# BoardA-USB.net
KiCad netlist of a schematic drawn in Altium Designer
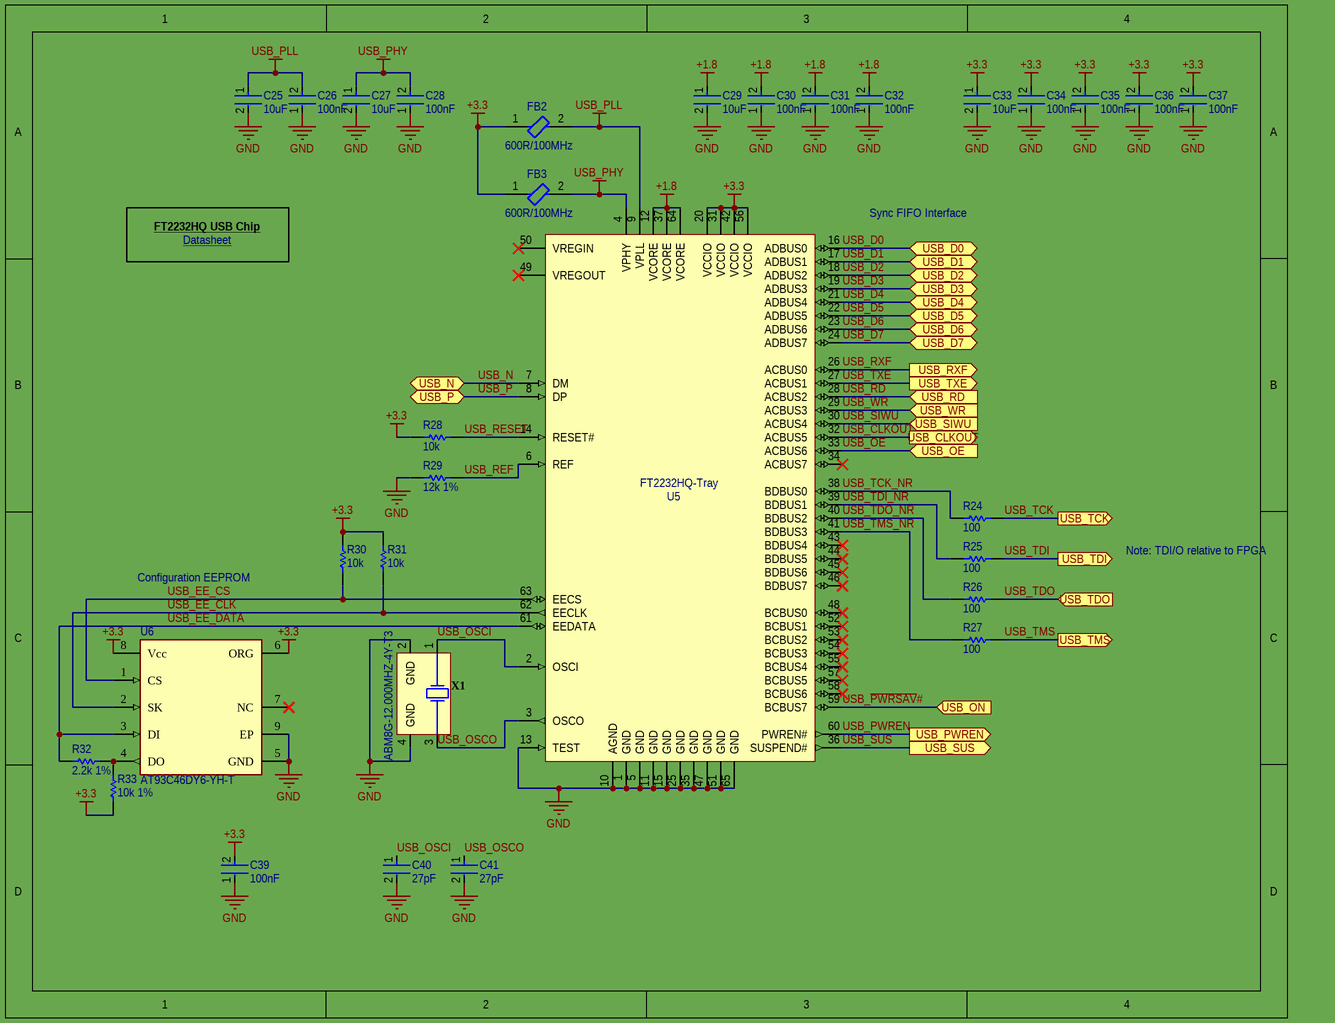
[diagram p0: BoardA-USB.SchDoc]

(export (version "E")
  (design (tool "Eeschema 10.0.6"))
  (components
    (comp (ref "C25")
      (value "10uF")
      (footprint "FP-CL05A106MP5NUNC-IPC_C")
      (description "CAP CER 10UF 10V X5R 0402")
      (fields
        (field (name "OCTOPART") "https://octopart.com/cl05a106mp5nunc-samsung-22457395")
        (field (name "TOLERANCE") "20%")
      )
      (libsource (lib "Altium Content Vault") (part "b4654b650e69147ec39a6b967a45e02"))
    )
    (comp (ref "C26")
      (value "100nF")
      (footprint "FP-GRM15-IPC_C")
      (description "CAP CER 0.1UF 16V X7R 0402")
      (fields (field (name "MANUFACTURER PART NUMBER") "GRM155R71C104KA88D") (field (name "TOLERANCE") "10%"))
      (libsource (lib "Altium Content Vault") (part "236180d848d6139a670b325ea6854c9"))
    )
    (comp (ref "C27")
      (value "10uF")
      (footprint "FP-CL05A106MP5NUNC-IPC_C")
      (description "CAP CER 10UF 10V X5R 0402")
      (fields
        (field (name "OCTOPART") "https://octopart.com/cl05a106mp5nunc-samsung-22457395")
        (field (name "TOLERANCE") "20%")
      )
      (libsource (lib "Altium Content Vault") (part "b4654b650e69147ec39a6b967a45e02"))
    )
    (comp (ref "C28")
      (value "100nF")
      (footprint "FP-GRM15-IPC_C")
      (description "CAP CER 0.1UF 16V X7R 0402")
      (fields (field (name "MANUFACTURER PART NUMBER") "GRM155R71C104KA88D") (field (name "TOLERANCE") "10%"))
      (libsource (lib "Altium Content Vault") (part "236180d848d6139a670b325ea6854c9"))
    )
    (comp (ref "C29")
      (value "10uF")
      (footprint "FP-CL05A106MP5NUNC-IPC_C")
      (description "CAP CER 10UF 10V X5R 0402")
      (fields
        (field (name "OCTOPART") "https://octopart.com/cl05a106mp5nunc-samsung-22457395")
        (field (name "TOLERANCE") "20%")
      )
      (libsource (lib "Altium Content Vault") (part "b4654b650e69147ec39a6b967a45e02"))
    )
    (comp (ref "C30")
      (value "100nF")
      (footprint "FP-GRM15-IPC_C")
      (description "CAP CER 0.1UF 16V X7R 0402")
      (fields (field (name "MANUFACTURER PART NUMBER") "GRM155R71C104KA88D") (field (name "TOLERANCE") "10%"))
      (libsource (lib "Altium Content Vault") (part "236180d848d6139a670b325ea6854c9"))
    )
    (comp (ref "C31")
      (value "100nF")
      (footprint "FP-GRM15-IPC_C")
      (description "CAP CER 0.1UF 16V X7R 0402")
      (fields (field (name "MANUFACTURER PART NUMBER") "GRM155R71C104KA88D") (field (name "TOLERANCE") "10%"))
      (libsource (lib "Altium Content Vault") (part "236180d848d6139a670b325ea6854c9"))
    )
    (comp (ref "C32")
      (value "100nF")
      (footprint "FP-GRM15-IPC_C")
      (description "CAP CER 0.1UF 16V X7R 0402")
      (fields (field (name "MANUFACTURER PART NUMBER") "GRM155R71C104KA88D") (field (name "TOLERANCE") "10%"))
      (libsource (lib "Altium Content Vault") (part "236180d848d6139a670b325ea6854c9"))
    )
    (comp (ref "C33")
      (value "10uF")
      (footprint "FP-CL05A106MP5NUNC-IPC_C")
      (description "CAP CER 10UF 10V X5R 0402")
      (fields
        (field (name "OCTOPART") "https://octopart.com/cl05a106mp5nunc-samsung-22457395")
        (field (name "TOLERANCE") "20%")
      )
      (libsource (lib "Altium Content Vault") (part "b4654b650e69147ec39a6b967a45e02"))
    )
    (comp (ref "C34")
      (value "100nF")
      (footprint "FP-GRM15-IPC_C")
      (description "CAP CER 0.1UF 16V X7R 0402")
      (fields (field (name "MANUFACTURER PART NUMBER") "GRM155R71C104KA88D") (field (name "TOLERANCE") "10%"))
      (libsource (lib "Altium Content Vault") (part "236180d848d6139a670b325ea6854c9"))
    )
    (comp (ref "C35")
      (value "100nF")
      (footprint "FP-GRM15-IPC_C")
      (description "CAP CER 0.1UF 16V X7R 0402")
      (fields (field (name "MANUFACTURER PART NUMBER") "GRM155R71C104KA88D") (field (name "TOLERANCE") "10%"))
      (libsource (lib "Altium Content Vault") (part "236180d848d6139a670b325ea6854c9"))
    )
    (comp (ref "C36")
      (value "100nF")
      (footprint "FP-GRM15-IPC_C")
      (description "CAP CER 0.1UF 16V X7R 0402")
      (fields (field (name "MANUFACTURER PART NUMBER") "GRM155R71C104KA88D") (field (name "TOLERANCE") "10%"))
      (libsource (lib "Altium Content Vault") (part "236180d848d6139a670b325ea6854c9"))
    )
    (comp (ref "C37")
      (value "100nF")
      (footprint "FP-GRM15-IPC_C")
      (description "CAP CER 0.1UF 16V X7R 0402")
      (fields (field (name "MANUFACTURER PART NUMBER") "GRM155R71C104KA88D") (field (name "TOLERANCE") "10%"))
      (libsource (lib "Altium Content Vault") (part "236180d848d6139a670b325ea6854c9"))
    )
    (comp (ref "C39")
      (value "100nF")
      (footprint "FP-GRM15-IPC_C")
      (description "CAP CER 0.1UF 16V X7R 0402")
      (fields (field (name "MANUFACTURER PART NUMBER") "GRM155R71C104KA88D") (field (name "TOLERANCE") "10%"))
      (libsource (lib "Altium Content Vault") (part "236180d848d6139a670b325ea6854c9"))
    )
    (comp (ref "C40")
      (value "27pF")
      (footprint "FP-C0402-BB-MFG")
      (description "CAP CER 27PF 50V C0G/NP0 0402")
      (fields (field (name "MANUFACTURER") "Kemet") (field (name "TOLERANCE") "0.05"))
      (libsource (lib "Altium Content Vault") (part "b4654b650e69147ec39a6b967a45e02"))
    )
    (comp (ref "C41")
      (value "27pF")
      (footprint "FP-C0402-BB-MFG")
      (description "CAP CER 27PF 50V C0G/NP0 0402")
      (fields (field (name "MANUFACTURER") "Kemet") (field (name "TOLERANCE") "0.05"))
      (libsource (lib "Altium Content Vault") (part "b4654b650e69147ec39a6b967a45e02"))
    )
    (comp (ref "FB2")
      (value "600R/100MHz")
      (footprint "FP-BLM18-0_15-t0_8-MFG")
      (description "Chip Ferrite Bead, 0603, 600Ω @ 100MHz, 0.38Ω, 25%, 500mA")
      (fields (field (name "TOLERANCE") "25%"))
      (libsource (lib "Altium Content Vault") (part "5f30dd21d616792df468990f7003faa"))
    )
    (comp (ref "FB3")
      (value "600R/100MHz")
      (footprint "FP-BLM18-0_15-t0_8-MFG")
      (description "Chip Ferrite Bead, 0603, 600Ω @ 100MHz, 0.38Ω, 25%, 500mA")
      (fields (field (name "TOLERANCE") "25%"))
      (libsource (lib "Altium Content Vault") (part "5f30dd21d616792df468990f7003faa"))
    )
    (comp (ref "R24")
      (value "100")
      (footprint "RESC1005X40X25LL05T10")
      (fields (field (name "PART NUMBER") "RC0402FR-07100RL") (field (name "MANUFACTURER") "Yageo / Phycomp"))
      (libsource (lib "Altium Content Vault") (part "RES"))
    )
    (comp (ref "R25")
      (value "100")
      (footprint "RESC1005X40X25LL05T10")
      (fields (field (name "PART NUMBER") "RC0402FR-07100RL") (field (name "MANUFACTURER") "Yageo / Phycomp"))
      (libsource (lib "Altium Content Vault") (part "RES"))
    )
    (comp (ref "R26")
      (value "100")
      (footprint "RESC1005X40X25LL05T10")
      (fields (field (name "PART NUMBER") "RC0402FR-07100RL") (field (name "MANUFACTURER") "Yageo / Phycomp"))
      (libsource (lib "Altium Content Vault") (part "RES"))
    )
    (comp (ref "R27")
      (value "100")
      (footprint "RESC1005X40X25LL05T10")
      (fields (field (name "PART NUMBER") "RC0402FR-07100RL") (field (name "MANUFACTURER") "Yageo / Phycomp"))
      (libsource (lib "Altium Content Vault") (part "RES"))
    )
    (comp (ref "R28")
      (value "10k")
      (footprint "RESC1005X40X25LL05T05")
      (description "Chip Resistor, 10 KOhm, +/- 1%, 0.1 W, -55 to 155 degC, 0402 (1005 Metric), RoHS, Tape and Reel")
      (fields (field (name "TOLERANCE") "1%") (field (name "MANUFACTURER") "Panasonic"))
      (libsource (lib "Altium Content Vault") (part "RES-2"))
    )
    (comp (ref "R29")
      (value "12k 1%")
      (footprint "RESC1005X40X25LL05T05")
      (description "Chip Resistor, 12 KOhm, +/- 1%, 0.1 W, -55 to 155 degC, 0402 (1005 Metric), RoHS, Tape and Reel")
      (fields (field (name "TOLERANCE") "1%") (field (name "PARTNUMBER") "ERJ-2RKF1202X"))
      (libsource (lib "Altium Content Vault") (part "RES-2"))
    )
    (comp (ref "R30")
      (value "10k")
      (footprint "RESC1005X40X25LL05T05")
      (description "Chip Resistor, 10 KOhm, +/- 1%, 0.1 W, -55 to 155 degC, 0402 (1005 Metric), RoHS, Tape and Reel")
      (fields (field (name "TOLERANCE") "1%") (field (name "MANUFACTURER") "Panasonic"))
      (libsource (lib "Altium Content Vault") (part "RES-2"))
    )
    (comp (ref "R31")
      (value "10k")
      (footprint "RESC1005X40X25LL05T05")
      (description "Chip Resistor, 10 KOhm, +/- 1%, 0.1 W, -55 to 155 degC, 0402 (1005 Metric), RoHS, Tape and Reel")
      (fields (field (name "TOLERANCE") "1%") (field (name "MANUFACTURER") "Panasonic"))
      (libsource (lib "Altium Content Vault") (part "RES-2"))
    )
    (comp (ref "R32")
      (value "2.2k 1%")
      (footprint "RESC1005X40X25NL05T10")
      (fields (field (name "MANUFACTURER") "Yageo / Phycomp") (field (name "PART NUMBER") "RC0402FR-072K2L"))
      (libsource (lib "Altium Content Vault") (part "RES"))
    )
    (comp (ref "R33")
      (value "10k 1%")
      (footprint "RESC1005X40X25LL05T05")
      (description "Chip Resistor, 10 KOhm, +/- 1%, 0.1 W, -55 to 155 degC, 0402 (1005 Metric), RoHS, Tape and Reel")
      (fields (field (name "TOLERANCE") "1%") (field (name "MANUFACTURER") "Panasonic"))
      (libsource (lib "Altium Content Vault") (part "RES-2"))
    )
    (comp (ref "U5")
      (value "FT2232HQ-Tray")
      (footprint "QFN64_2_N")
      (description "Dual High Speed USB To Multipurpose UART/FIFO IC, 64-pin QFN, Tray")
      (fields (field (name "MANUFACTURER") "FTDI"))
      (libsource (lib "Altium Content Vault") (part "COM-UART-FT2232H-QFN64"))
    )
    (comp (ref "U6")
      (value "AT93C46DY6-YH-T")
      (footprint "FP-C04-21355-Q4B-IPC_C")
      (description "IC EEPROM 1KBIT SPI 8MINI MAP")
      (libsource (lib "Altium Content Vault") (part "38d5b16ef365a7a64ac37fa7d10f17c"))
    )
    (comp (ref "X1")
      (value "ABM8G-12.000MHZ-4Y-T3")
      (footprint "ABM8G-12.000MHZ-4Y-T3")
      (description "ABRACON - ABM8G-12.000MHZ-4Y-T3 - CRYSTAL, 12MHZ, 10PF, 3.2 X 2.5MM")
      (fields (field (name "MANUFACTURER") "Abracon"))
      (libsource (lib "Virtex") (part "ABM8G-12.000MHZ-4Y-T3"))
    )
  )
  (nets
    (net (code "1") (name "+1.8") (class "Default")
      (node (ref "C29") (pin "1") (pinfunction "1_1") (pintype "passive"))
      (node (ref "C30") (pin "2") (pinfunction "2_2") (pintype "passive"))
      (node (ref "C31") (pin "2") (pinfunction "2_2") (pintype "passive"))
      (node (ref "C32") (pin "2") (pinfunction "2_2") (pintype "passive"))
      (node (ref "U5") (pin "12") (pinfunction "VCORE_12") (pintype "power_in"))
      (node (ref "U5") (pin "37") (pinfunction "VCORE_37") (pintype "power_in"))
      (node (ref "U5") (pin "64") (pinfunction "VCORE_64") (pintype "power_in"))
    )
    (net (code "2") (name "+3.3") (class "Default")
      (node (ref "C33") (pin "1") (pinfunction "1_1") (pintype "passive"))
      (node (ref "C34") (pin "2") (pinfunction "2_2") (pintype "passive"))
      (node (ref "C35") (pin "2") (pinfunction "2_2") (pintype "passive"))
      (node (ref "C36") (pin "2") (pinfunction "2_2") (pintype "passive"))
      (node (ref "C37") (pin "2") (pinfunction "2_2") (pintype "passive"))
      (node (ref "C39") (pin "2") (pinfunction "2_2") (pintype "passive"))
      (node (ref "FB2") (pin "1") (pinfunction "1_1") (pintype "passive"))
      (node (ref "FB3") (pin "1") (pinfunction "1_1") (pintype "passive"))
      (node (ref "R28") (pin "2") (pinfunction "2_2") (pintype "passive"))
      (node (ref "R30") (pin "2") (pinfunction "2_2") (pintype "passive"))
      (node (ref "R31") (pin "2") (pinfunction "2_2") (pintype "passive"))
      (node (ref "R33") (pin "1") (pinfunction "1_1") (pintype "passive"))
      (node (ref "U5") (pin "20") (pinfunction "VCCIO_20") (pintype "power_in"))
      (node (ref "U5") (pin "31") (pinfunction "VCCIO_31") (pintype "power_in"))
      (node (ref "U5") (pin "42") (pinfunction "VCCIO_42") (pintype "power_in"))
      (node (ref "U5") (pin "56") (pinfunction "VCCIO_56") (pintype "power_in"))
      (node (ref "U6") (pin "6") (pinfunction "ORG_6") (pintype "passive"))
      (node (ref "U6") (pin "8") (pinfunction "Vcc_8") (pintype "power_in"))
    )
    (net (code "3") (name "/USB_CLKOUT") (class "Default")
      (node (ref "U5") (pin "32") (pinfunction "ACBUS5_32") (pintype "bidirectional"))
    )
    (net (code "4") (name "/USB_D0") (class "Default")
      (node (ref "U5") (pin "16") (pinfunction "ADBUS0_16") (pintype "bidirectional"))
    )
    (net (code "5") (name "/USB_D1") (class "Default")
      (node (ref "U5") (pin "17") (pinfunction "ADBUS1_17") (pintype "bidirectional"))
    )
    (net (code "6") (name "/USB_D2") (class "Default")
      (node (ref "U5") (pin "18") (pinfunction "ADBUS2_18") (pintype "bidirectional"))
    )
    (net (code "7") (name "/USB_D3") (class "Default")
      (node (ref "U5") (pin "19") (pinfunction "ADBUS3_19") (pintype "bidirectional"))
    )
    (net (code "8") (name "/USB_D4") (class "Default")
      (node (ref "U5") (pin "21") (pinfunction "ADBUS4_21") (pintype "bidirectional"))
    )
    (net (code "9") (name "/USB_D5") (class "Default")
      (node (ref "U5") (pin "22") (pinfunction "ADBUS5_22") (pintype "bidirectional"))
    )
    (net (code "10") (name "/USB_D6") (class "Default")
      (node (ref "U5") (pin "23") (pinfunction "ADBUS6_23") (pintype "bidirectional"))
    )
    (net (code "11") (name "/USB_D7") (class "Default")
      (node (ref "U5") (pin "24") (pinfunction "ADBUS7_24") (pintype "bidirectional"))
    )
    (net (code "12") (name "/USB_EE_CLK") (class "Default")
      (node (ref "R31") (pin "1") (pinfunction "1_1") (pintype "passive"))
      (node (ref "U5") (pin "62") (pinfunction "EECLK_62") (pintype "output"))
      (node (ref "U6") (pin "2") (pinfunction "SK_2") (pintype "input"))
    )
    (net (code "13") (name "/USB_EE_CS") (class "Default")
      (node (ref "R30") (pin "1") (pinfunction "1_1") (pintype "passive"))
      (node (ref "U5") (pin "63") (pinfunction "EECS_63") (pintype "bidirectional"))
      (node (ref "U6") (pin "1") (pinfunction "CS_1") (pintype "input"))
    )
    (net (code "14") (name "/USB_EE_DATA") (class "Default")
      (node (ref "R32") (pin "1") (pinfunction "1_1") (pintype "passive"))
      (node (ref "U5") (pin "61") (pinfunction "EEDATA_61") (pintype "bidirectional"))
      (node (ref "U6") (pin "3") (pinfunction "DI_3") (pintype "input"))
    )
    (net (code "15") (name "/USB_N") (class "Default")
      (node (ref "U5") (pin "7") (pinfunction "DM_7") (pintype "input"))
    )
    (net (code "16") (name "/USB_OE") (class "Default")
      (node (ref "U5") (pin "33") (pinfunction "ACBUS6_33") (pintype "bidirectional"))
    )
    (net (code "17") (name "/USB_OSCI") (class "Default")
      (node (ref "C40") (pin "1") (pinfunction "1_1") (pintype "passive"))
      (node (ref "U5") (pin "2") (pinfunction "OSCI_2") (pintype "input"))
      (node (ref "X1") (pin "1") (pintype "passive"))
    )
    (net (code "18") (name "/USB_OSCO") (class "Default")
      (node (ref "C41") (pin "1") (pinfunction "1_1") (pintype "passive"))
      (node (ref "U5") (pin "3") (pinfunction "OSCO_3") (pintype "output"))
      (node (ref "X1") (pin "3") (pintype "passive"))
    )
    (net (code "19") (name "/USB_P") (class "Default")
      (node (ref "U5") (pin "8") (pinfunction "DP_8") (pintype "input"))
    )
    (net (code "20") (name "/USB_PWREN") (class "Default")
      (node (ref "U5") (pin "60") (pinfunction "PWREN#_60") (pintype "output"))
    )
    (net (code "21") (name "/USB_RD") (class "Default")
      (node (ref "U5") (pin "28") (pinfunction "ACBUS2_28") (pintype "bidirectional"))
    )
    (net (code "22") (name "/USB_REF") (class "Default")
      (node (ref "R29") (pin "2") (pinfunction "2_2") (pintype "passive"))
      (node (ref "U5") (pin "6") (pinfunction "REF_6") (pintype "input"))
    )
    (net (code "23") (name "/USB_RESET") (class "Default")
      (node (ref "R28") (pin "1") (pinfunction "1_1") (pintype "passive"))
      (node (ref "U5") (pin "14") (pinfunction "RESET#_14") (pintype "input"))
    )
    (net (code "24") (name "/USB_RXF") (class "Default")
      (node (ref "U5") (pin "26") (pinfunction "ACBUS0_26") (pintype "bidirectional"))
    )
    (net (code "25") (name "/USB_SIWU") (class "Default")
      (node (ref "U5") (pin "30") (pinfunction "ACBUS4_30") (pintype "bidirectional"))
    )
    (net (code "26") (name "/USB_SUS") (class "Default")
      (node (ref "U5") (pin "36") (pinfunction "SUSPEND#_36") (pintype "output"))
    )
    (net (code "27") (name "/USB_TCK") (class "Default")
      (node (ref "R24") (pin "2") (pinfunction "2_2") (pintype "passive"))
    )
    (net (code "28") (name "/USB_TCK_NR") (class "Default")
      (node (ref "R24") (pin "1") (pinfunction "1_1") (pintype "passive"))
      (node (ref "U5") (pin "38") (pinfunction "BDBUS0_38") (pintype "bidirectional"))
    )
    (net (code "29") (name "/USB_TDI") (class "Default")
      (node (ref "R25") (pin "2") (pinfunction "2_2") (pintype "passive"))
    )
    (net (code "30") (name "/USB_TDI_NR") (class "Default")
      (node (ref "R25") (pin "1") (pinfunction "1_1") (pintype "passive"))
      (node (ref "U5") (pin "39") (pinfunction "BDBUS1_39") (pintype "bidirectional"))
    )
    (net (code "31") (name "/USB_TDO") (class "Default")
      (node (ref "R26") (pin "2") (pinfunction "2_2") (pintype "passive"))
    )
    (net (code "32") (name "/USB_TDO_NR") (class "Default")
      (node (ref "R26") (pin "1") (pinfunction "1_1") (pintype "passive"))
      (node (ref "U5") (pin "40") (pinfunction "BDBUS2_40") (pintype "bidirectional"))
    )
    (net (code "33") (name "/USB_TMS") (class "Default")
      (node (ref "R27") (pin "2") (pinfunction "2_2") (pintype "passive"))
    )
    (net (code "34") (name "/USB_TMS_NR") (class "Default")
      (node (ref "R27") (pin "1") (pinfunction "1_1") (pintype "passive"))
      (node (ref "U5") (pin "41") (pinfunction "BDBUS3_41") (pintype "bidirectional"))
    )
    (net (code "35") (name "/USB_TXE") (class "Default")
      (node (ref "U5") (pin "27") (pinfunction "ACBUS1_27") (pintype "bidirectional"))
    )
    (net (code "36") (name "/USB_WR") (class "Default")
      (node (ref "U5") (pin "29") (pinfunction "ACBUS3_29") (pintype "bidirectional"))
    )
    (net (code "37") (name "/USB_~{PWRSAV}#") (class "Default")
      (node (ref "U5") (pin "59") (pinfunction "BCBUS7_59") (pintype "bidirectional"))
    )
    (net (code "38") (name "GND") (class "Default")
      (node (ref "C25") (pin "2") (pinfunction "2_2") (pintype "passive"))
      (node (ref "C26") (pin "1") (pinfunction "1_1") (pintype "passive"))
      (node (ref "C27") (pin "2") (pinfunction "2_2") (pintype "passive"))
      (node (ref "C28") (pin "1") (pinfunction "1_1") (pintype "passive"))
      (node (ref "C29") (pin "2") (pinfunction "2_2") (pintype "passive"))
      (node (ref "C30") (pin "1") (pinfunction "1_1") (pintype "passive"))
      (node (ref "C31") (pin "1") (pinfunction "1_1") (pintype "passive"))
      (node (ref "C32") (pin "1") (pinfunction "1_1") (pintype "passive"))
      (node (ref "C33") (pin "2") (pinfunction "2_2") (pintype "passive"))
      (node (ref "C34") (pin "1") (pinfunction "1_1") (pintype "passive"))
      (node (ref "C35") (pin "1") (pinfunction "1_1") (pintype "passive"))
      (node (ref "C36") (pin "1") (pinfunction "1_1") (pintype "passive"))
      (node (ref "C37") (pin "1") (pinfunction "1_1") (pintype "passive"))
      (node (ref "C39") (pin "1") (pinfunction "1_1") (pintype "passive"))
      (node (ref "C40") (pin "2") (pinfunction "2_2") (pintype "passive"))
      (node (ref "C41") (pin "2") (pinfunction "2_2") (pintype "passive"))
      (node (ref "R29") (pin "1") (pinfunction "1_1") (pintype "passive"))
      (node (ref "U5") (pin "1") (pinfunction "GND_1") (pintype "power_in"))
      (node (ref "U5") (pin "10") (pinfunction "AGND_10") (pintype "power_in"))
      (node (ref "U5") (pin "11") (pinfunction "GND_11") (pintype "power_in"))
      (node (ref "U5") (pin "13") (pinfunction "TEST_13") (pintype "input"))
      (node (ref "U5") (pin "15") (pinfunction "GND_15") (pintype "power_in"))
      (node (ref "U5") (pin "25") (pinfunction "GND_25") (pintype "power_in"))
      (node (ref "U5") (pin "35") (pinfunction "GND_35") (pintype "power_in"))
      (node (ref "U5") (pin "47") (pinfunction "GND_47") (pintype "power_in"))
      (node (ref "U5") (pin "5") (pinfunction "GND_5") (pintype "power_in"))
      (node (ref "U5") (pin "51") (pinfunction "GND_51") (pintype "power_in"))
      (node (ref "U5") (pin "65") (pinfunction "GND_65") (pintype "power_in"))
      (node (ref "U6") (pin "5") (pinfunction "GND_5") (pintype "power_in"))
      (node (ref "U6") (pin "9") (pinfunction "EP_9") (pintype "passive"))
      (node (ref "X1") (pin "2") (pinfunction "GND_2") (pintype "power_in"))
      (node (ref "X1") (pin "4") (pinfunction "GND_4") (pintype "power_in"))
    )
    (net (code "39") (name "Net-(U6-DO)") (class "Default")
      (node (ref "R32") (pin "2") (pinfunction "2_2") (pintype "passive"))
      (node (ref "R33") (pin "2") (pinfunction "2_2") (pintype "passive"))
      (node (ref "U6") (pin "4") (pinfunction "DO_4") (pintype "output"))
    )
    (net (code "40") (name "USB_PHY") (class "Default")
      (node (ref "C27") (pin "1") (pinfunction "1_1") (pintype "passive"))
      (node (ref "C28") (pin "2") (pinfunction "2_2") (pintype "passive"))
      (node (ref "FB3") (pin "2") (pinfunction "2_2") (pintype "passive"))
      (node (ref "U5") (pin "4") (pinfunction "VPHY_4") (pintype "power_in"))
    )
    (net (code "41") (name "USB_PLL") (class "Default")
      (node (ref "C25") (pin "1") (pinfunction "1_1") (pintype "passive"))
      (node (ref "C26") (pin "2") (pinfunction "2_2") (pintype "passive"))
      (node (ref "FB2") (pin "2") (pinfunction "2_2") (pintype "passive"))
      (node (ref "U5") (pin "9") (pinfunction "VPLL_9") (pintype "power_in"))
    )
    (net (code "42") (name "unconnected-(U5-ACBUS7-Pad34)") (class "Default")
      (node (ref "U5") (pin "34") (pinfunction "ACBUS7_34") (pintype "bidirectional+no_connect"))
    )
    (net (code "43") (name "unconnected-(U5-BCBUS0-Pad48)") (class "Default")
      (node (ref "U5") (pin "48") (pinfunction "BCBUS0_48") (pintype "bidirectional+no_connect"))
    )
    (net (code "44") (name "unconnected-(U5-BCBUS1-Pad52)") (class "Default")
      (node (ref "U5") (pin "52") (pinfunction "BCBUS1_52") (pintype "bidirectional+no_connect"))
    )
    (net (code "45") (name "unconnected-(U5-BCBUS2-Pad53)") (class "Default")
      (node (ref "U5") (pin "53") (pinfunction "BCBUS2_53") (pintype "bidirectional+no_connect"))
    )
    (net (code "46") (name "unconnected-(U5-BCBUS3-Pad54)") (class "Default")
      (node (ref "U5") (pin "54") (pinfunction "BCBUS3_54") (pintype "bidirectional+no_connect"))
    )
    (net (code "47") (name "unconnected-(U5-BCBUS4-Pad55)") (class "Default")
      (node (ref "U5") (pin "55") (pinfunction "BCBUS4_55") (pintype "bidirectional+no_connect"))
    )
    (net (code "48") (name "unconnected-(U5-BCBUS5-Pad57)") (class "Default")
      (node (ref "U5") (pin "57") (pinfunction "BCBUS5_57") (pintype "bidirectional+no_connect"))
    )
    (net (code "49") (name "unconnected-(U5-BCBUS6-Pad58)") (class "Default")
      (node (ref "U5") (pin "58") (pinfunction "BCBUS6_58") (pintype "bidirectional+no_connect"))
    )
    (net (code "50") (name "unconnected-(U5-BDBUS4-Pad43)") (class "Default")
      (node (ref "U5") (pin "43") (pinfunction "BDBUS4_43") (pintype "bidirectional+no_connect"))
    )
    (net (code "51") (name "unconnected-(U5-BDBUS5-Pad44)") (class "Default")
      (node (ref "U5") (pin "44") (pinfunction "BDBUS5_44") (pintype "bidirectional+no_connect"))
    )
    (net (code "52") (name "unconnected-(U5-BDBUS6-Pad45)") (class "Default")
      (node (ref "U5") (pin "45") (pinfunction "BDBUS6_45") (pintype "bidirectional+no_connect"))
    )
    (net (code "53") (name "unconnected-(U5-BDBUS7-Pad46)") (class "Default")
      (node (ref "U5") (pin "46") (pinfunction "BDBUS7_46") (pintype "bidirectional+no_connect"))
    )
    (net (code "54") (name "unconnected-(U5-VREGIN-Pad50)") (class "Default")
      (node (ref "U5") (pin "50") (pinfunction "VREGIN_50") (pintype "power_in+no_connect"))
    )
    (net (code "55") (name "unconnected-(U5-VREGOUT-Pad49)") (class "Default")
      (node (ref "U5") (pin "49") (pinfunction "VREGOUT_49") (pintype "power_in+no_connect"))
    )
    (net (code "56") (name "unconnected-(U6-NC-Pad7)") (class "Default")
      (node (ref "U6") (pin "7") (pinfunction "NC_7") (pintype "passive+no_connect"))
    )
  )
)
